# Schematic.net
KiCad netlist of a schematic drawn in Altium Designer
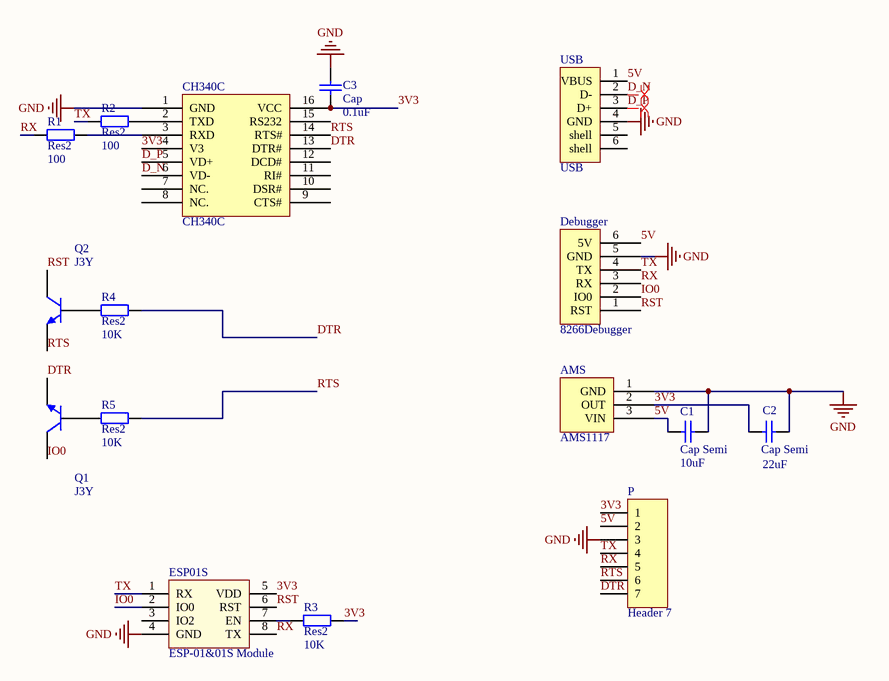
[diagram p0: Schematic.SchDoc]

(export (version "E")
  (design (tool "Eeschema 10.0.6"))
  (components
    (comp (ref "AMS") (value "AMS1117") (footprint "SOT-223-2") (libsource (lib "Schlib2") (part "AMS1117")))
    (comp (ref "C1")
      (value "Cap Semi")
      (footprint "C1206")
      (description "Capacitor (Semiconductor SIM Model)")
      (fields (field (name "ALTIUM_VALUE") "10uF") (field (name "PUBLISHER") "Altium Limited"))
      (libsource (lib "Miscellaneous Devices") (part "Cap Semi"))
    )
    (comp (ref "C2")
      (value "Cap Semi")
      (footprint "C1206")
      (description "Capacitor (Semiconductor SIM Model)")
      (fields (field (name "ALTIUM_VALUE") "22uF") (field (name "PUBLISHER") "Altium Limited"))
      (libsource (lib "Miscellaneous Devices") (part "Cap Semi"))
    )
    (comp (ref "C3")
      (value "Cap")
      (footprint "C1206")
      (description "Capacitor")
      (fields (field (name "ALTIUM_VALUE") "0.1uF") (field (name "PUBLISHER") "Altium Limited"))
      (libsource (lib "Miscellaneous Devices") (part "Cap"))
    )
    (comp (ref "CH340C") (value "CH340C") (footprint "SOP16") (libsource (lib "我的元件库") (part "CH340C")))
    (comp (ref "Debugger")
      (value "8266Debugger")
      (footprint "XH2.54-LI-6P")
      (libsource (lib "我的元件库") (part "8266Debugger"))
    )
    (comp (ref "ESP01S")
      (value "ESP-01&01S Module")
      (footprint "ESP-01&01S Module")
      (libsource (lib "ESP-01&01S Module") (part "ESP-01&01S Module"))
    )
    (comp (ref "P")
      (value "Header 7")
      (footprint "HDR1X7")
      (description "Header, 7-Pin")
      (fields (field (name "PUBLISHER") "Altium Limited"))
      (libsource (lib "Miscellaneous Connectors") (part "Header 7"))
    )
    (comp (ref "Q1")
      (value "J3Y")
      (footprint "SOT-23B_N")
      (description "NPN Bipolar Transistor")
      (fields (field (name "PUBLISHER") "Altium Limited"))
      (libsource (lib "Miscellaneous Devices") (part "QNPN"))
    )
    (comp (ref "Q2")
      (value "J3Y")
      (footprint "SOT-23B_N")
      (description "NPN Bipolar Transistor")
      (fields (field (name "PUBLISHER") "Altium Limited"))
      (libsource (lib "Miscellaneous Devices") (part "QNPN"))
    )
    (comp (ref "R1")
      (value "Res2")
      (footprint "c1206")
      (description "Resistor")
      (fields (field (name "ALTIUM_VALUE") "100") (field (name "PUBLISHER") "Altium Limited"))
      (libsource (lib "Miscellaneous Devices") (part "Res2"))
    )
    (comp (ref "R2")
      (value "Res2")
      (footprint "c1206")
      (description "Resistor")
      (fields (field (name "ALTIUM_VALUE") "100") (field (name "PUBLISHER") "Altium Limited"))
      (libsource (lib "Miscellaneous Devices") (part "Res2"))
    )
    (comp (ref "R3")
      (value "Res2")
      (footprint "c1206")
      (description "Resistor")
      (fields (field (name "ALTIUM_VALUE") "10K") (field (name "PUBLISHER") "Altium Limited"))
      (libsource (lib "") (part "Res2_1"))
    )
    (comp (ref "R4")
      (value "Res2")
      (footprint "c1206")
      (description "Resistor")
      (fields (field (name "ALTIUM_VALUE") "10K") (field (name "PUBLISHER") "Altium Limited"))
      (libsource (lib "Miscellaneous Devices") (part "Res2"))
    )
    (comp (ref "R5")
      (value "Res2")
      (footprint "c1206")
      (description "Resistor")
      (fields (field (name "ALTIUM_VALUE") "10K") (field (name "PUBLISHER") "Altium Limited"))
      (libsource (lib "Miscellaneous Devices") (part "Res2"))
    )
    (comp (ref "USB") (value "USB") (footprint "USB-B") (libsource (lib "我的元件库") (part "USB")))
  )
  (nets
    (net (code "1") (name "/3V3") (class "Default")
      (node (ref "AMS") (pin "2") (pinfunction "OUT_2") (pintype "passive"))
      (node (ref "C2") (pin "1") (pinfunction "1_1") (pintype "passive"))
      (node (ref "C3") (pin "1") (pinfunction "1_1") (pintype "passive"))
      (node (ref "CH340C") (pin "16") (pinfunction "VCC_16") (pintype "passive"))
      (node (ref "CH340C") (pin "4") (pinfunction "V3_4") (pintype "passive"))
      (node (ref "ESP01S") (pin "5") (pinfunction "VDD_5") (pintype "passive"))
      (node (ref "P") (pin "1") (pinfunction "1_1") (pintype "passive"))
      (node (ref "R3") (pin "1") (pinfunction "1_1") (pintype "passive"))
    )
    (net (code "2") (name "/5V") (class "Default")
      (node (ref "AMS") (pin "3") (pinfunction "VIN_3") (pintype "passive"))
      (node (ref "C1") (pin "1") (pinfunction "1_1") (pintype "passive"))
      (node (ref "Debugger") (pin "6") (pinfunction "5V_6") (pintype "passive"))
      (node (ref "P") (pin "2") (pinfunction "2_2") (pintype "passive"))
      (node (ref "USB") (pin "1") (pinfunction "VBUS_1") (pintype "passive"))
    )
    (net (code "3") (name "/DTR") (class "Default")
      (node (ref "CH340C") (pin "13") (pinfunction "DTR#_13") (pintype "passive"))
      (node (ref "P") (pin "7") (pinfunction "7_7") (pintype "passive"))
      (node (ref "Q1") (pin "3") (pinfunction "E_3") (pintype "passive"))
      (node (ref "R4") (pin "2") (pinfunction "2_2") (pintype "passive"))
    )
    (net (code "4") (name "/D_N") (class "Default")
      (node (ref "CH340C") (pin "6") (pinfunction "VD-_6") (pintype "passive"))
      (node (ref "USB") (pin "2") (pinfunction "D-_2") (pintype "passive"))
    )
    (net (code "5") (name "/D_P") (class "Default")
      (node (ref "CH340C") (pin "5") (pinfunction "VD+_5") (pintype "passive"))
      (node (ref "USB") (pin "3") (pinfunction "D+_3") (pintype "passive"))
    )
    (net (code "6") (name "/IO0") (class "Default")
      (node (ref "Debugger") (pin "2") (pinfunction "IO0_2") (pintype "passive"))
      (node (ref "ESP01S") (pin "2") (pinfunction "IO0_2") (pintype "passive"))
      (node (ref "Q1") (pin "1") (pinfunction "C_1") (pintype "passive"))
    )
    (net (code "7") (name "/RST") (class "Default")
      (node (ref "Debugger") (pin "1") (pinfunction "RST_1") (pintype "passive"))
      (node (ref "ESP01S") (pin "6") (pinfunction "RST_6") (pintype "passive"))
      (node (ref "Q2") (pin "1") (pinfunction "C_1") (pintype "passive"))
    )
    (net (code "8") (name "/RTS") (class "Default")
      (node (ref "CH340C") (pin "14") (pinfunction "RTS#_14") (pintype "passive"))
      (node (ref "P") (pin "6") (pinfunction "6_6") (pintype "passive"))
      (node (ref "Q2") (pin "3") (pinfunction "E_3") (pintype "passive"))
      (node (ref "R5") (pin "2") (pinfunction "2_2") (pintype "passive"))
    )
    (net (code "9") (name "/RX") (class "Default")
      (node (ref "Debugger") (pin "3") (pinfunction "RX_3") (pintype "passive"))
      (node (ref "ESP01S") (pin "8") (pinfunction "TX_8") (pintype "passive"))
      (node (ref "P") (pin "5") (pinfunction "5_5") (pintype "passive"))
      (node (ref "R1") (pin "1") (pinfunction "1_1") (pintype "passive"))
    )
    (net (code "10") (name "/TX") (class "Default")
      (node (ref "Debugger") (pin "4") (pinfunction "TX_4") (pintype "passive"))
      (node (ref "ESP01S") (pin "1") (pinfunction "RX_1") (pintype "passive"))
      (node (ref "P") (pin "4") (pinfunction "4_4") (pintype "passive"))
      (node (ref "R2") (pin "1") (pinfunction "1_1") (pintype "passive"))
    )
    (net (code "11") (name "GND") (class "Default")
      (node (ref "AMS") (pin "1") (pinfunction "GND_1") (pintype "passive"))
      (node (ref "C1") (pin "2") (pinfunction "2_2") (pintype "passive"))
      (node (ref "C2") (pin "2") (pinfunction "2_2") (pintype "passive"))
      (node (ref "C3") (pin "2") (pinfunction "2_2") (pintype "passive"))
      (node (ref "CH340C") (pin "1") (pinfunction "GND_1") (pintype "passive"))
      (node (ref "Debugger") (pin "5") (pinfunction "GND_5") (pintype "passive"))
      (node (ref "ESP01S") (pin "4") (pinfunction "GND_4") (pintype "passive"))
      (node (ref "P") (pin "3") (pinfunction "3_3") (pintype "passive"))
      (node (ref "USB") (pin "4") (pinfunction "GND_4") (pintype "passive"))
    )
    (net (code "12") (name "Net-(CH340C-RXD)") (class "Default")
      (node (ref "CH340C") (pin "3") (pinfunction "RXD_3") (pintype "passive"))
      (node (ref "R1") (pin "2") (pinfunction "2_2") (pintype "passive"))
    )
    (net (code "13") (name "Net-(CH340C-TXD)") (class "Default")
      (node (ref "CH340C") (pin "2") (pinfunction "TXD_2") (pintype "passive"))
      (node (ref "R2") (pin "2") (pinfunction "2_2") (pintype "passive"))
    )
    (net (code "14") (name "Net-(ESP01S-EN)") (class "Default")
      (node (ref "ESP01S") (pin "7") (pinfunction "EN_7") (pintype "passive"))
      (node (ref "R3") (pin "2") (pinfunction "2_2") (pintype "passive"))
    )
    (net (code "15") (name "Net-(Q1-B)") (class "Default")
      (node (ref "Q1") (pin "2") (pinfunction "B_2") (pintype "passive"))
      (node (ref "R5") (pin "1") (pinfunction "1_1") (pintype "passive"))
    )
    (net (code "16") (name "Net-(Q2-B)") (class "Default")
      (node (ref "Q2") (pin "2") (pinfunction "B_2") (pintype "passive"))
      (node (ref "R4") (pin "1") (pinfunction "1_1") (pintype "passive"))
    )
    (net (code "17") (name "unconnected-(CH340C-CTS#-Pad9)") (class "Default")
      (node (ref "CH340C") (pin "9") (pinfunction "CTS#_9") (pintype "passive"))
    )
    (net (code "18") (name "unconnected-(CH340C-DCD#-Pad12)") (class "Default")
      (node (ref "CH340C") (pin "12") (pinfunction "DCD#_12") (pintype "passive"))
    )
    (net (code "19") (name "unconnected-(CH340C-DSR#-Pad10)") (class "Default")
      (node (ref "CH340C") (pin "10") (pinfunction "DSR#_10") (pintype "passive"))
    )
    (net (code "20") (name "unconnected-(CH340C-NC.-Pad7)") (class "Default")
      (node (ref "CH340C") (pin "7") (pinfunction "NC._7") (pintype "passive"))
    )
    (net (code "21") (name "unconnected-(CH340C-NC.-Pad8)") (class "Default")
      (node (ref "CH340C") (pin "8") (pinfunction "NC._8") (pintype "passive"))
    )
    (net (code "22") (name "unconnected-(CH340C-RI#-Pad11)") (class "Default")
      (node (ref "CH340C") (pin "11") (pinfunction "RI#_11") (pintype "passive"))
    )
    (net (code "23") (name "unconnected-(CH340C-RS232-Pad15)") (class "Default")
      (node (ref "CH340C") (pin "15") (pinfunction "RS232_15") (pintype "passive"))
    )
    (net (code "24") (name "unconnected-(ESP01S-IO2-Pad3)") (class "Default")
      (node (ref "ESP01S") (pin "3") (pinfunction "IO2_3") (pintype "passive"))
    )
    (net (code "25") (name "unconnected-(USB-shell-Pad5)") (class "Default")
      (node (ref "USB") (pin "5") (pinfunction "shell_5") (pintype "passive"))
    )
    (net (code "26") (name "unconnected-(USB-shell-Pad6)") (class "Default")
      (node (ref "USB") (pin "6") (pinfunction "shell_6") (pintype "passive"))
    )
  )
)
